# POWER_SUPPLY.net
KiCad netlist of a schematic drawn in Altium Designer
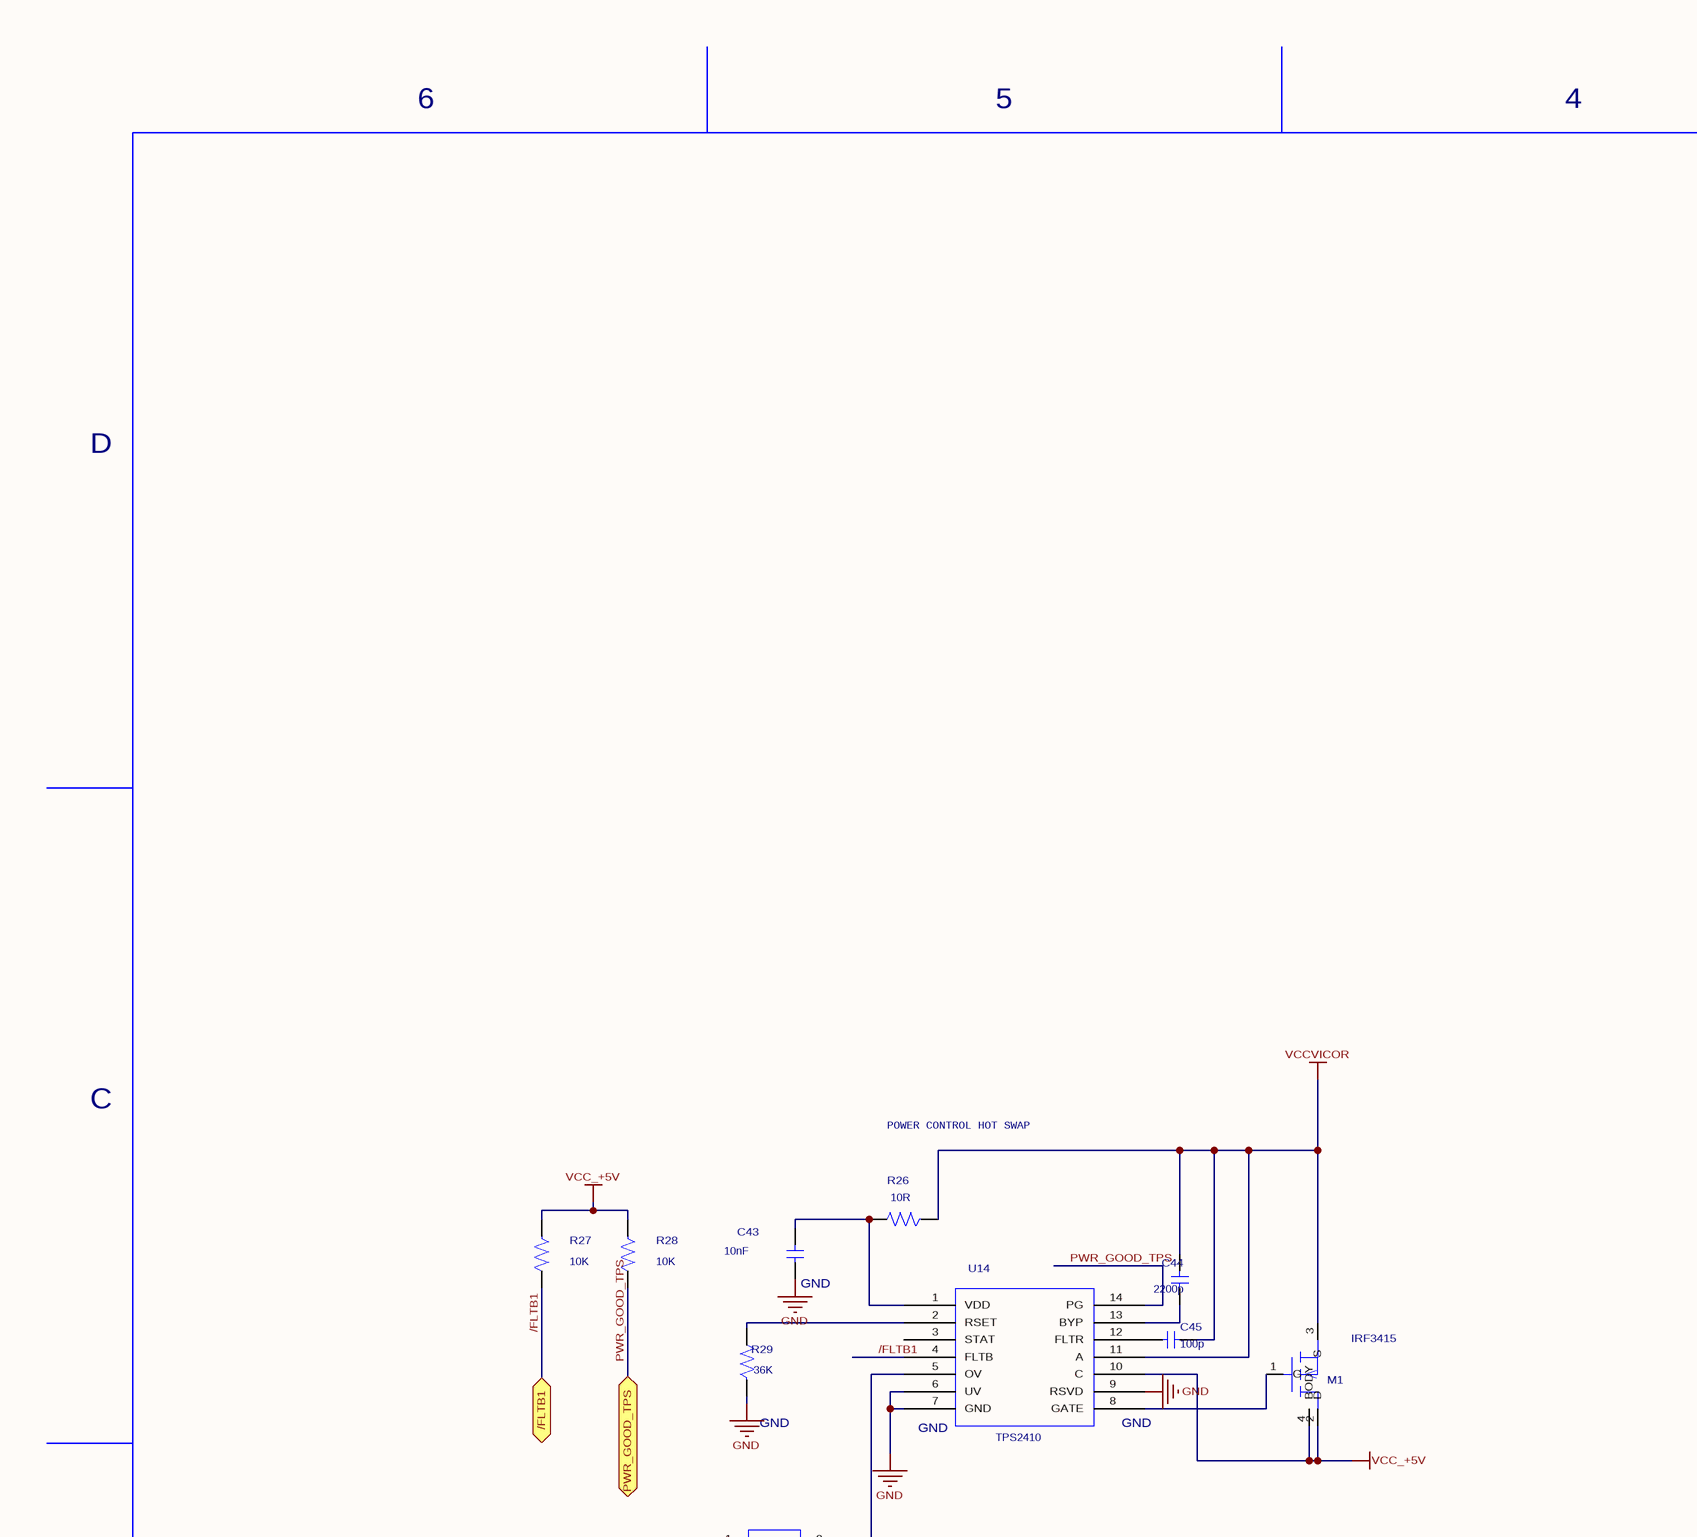
[diagram p0: POWER_SUPPLY.SchDoc, top left]
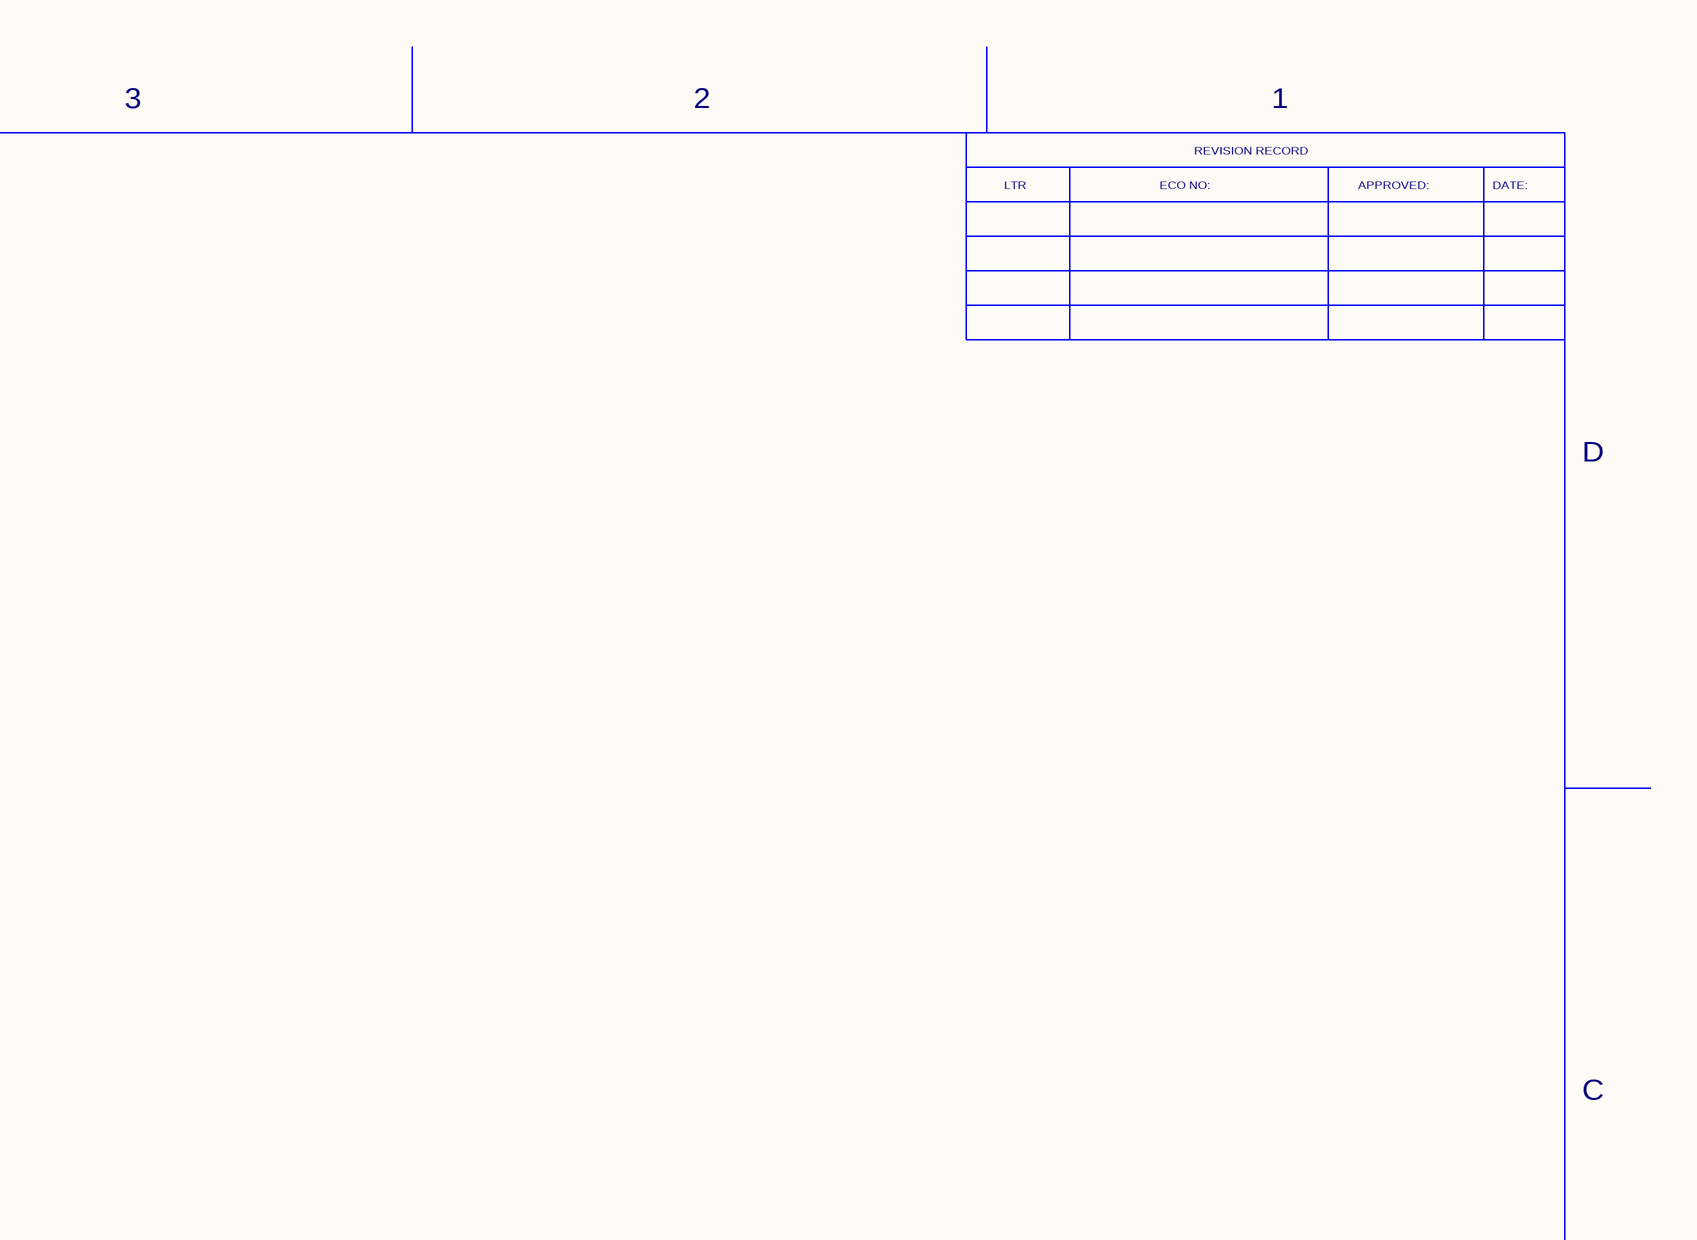
[diagram p1: POWER_SUPPLY.SchDoc, top right]
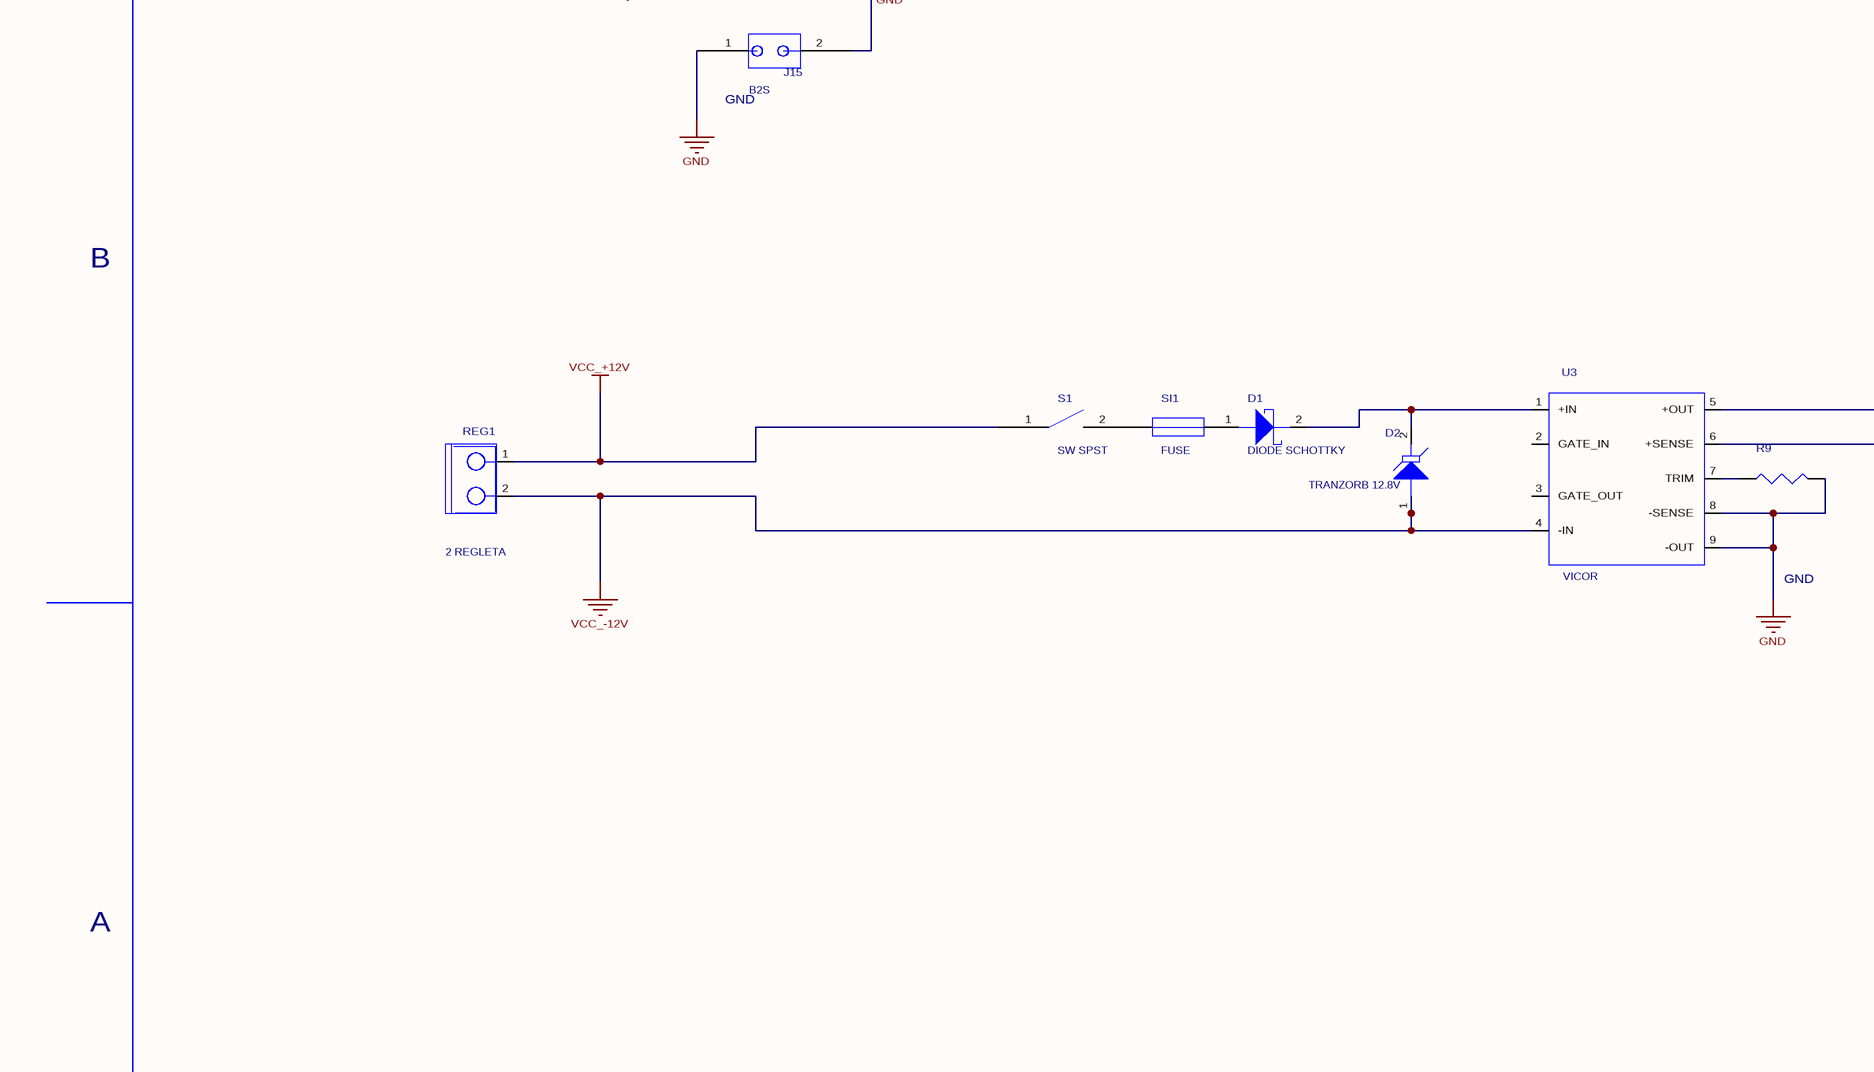
[diagram p2: POWER_SUPPLY.SchDoc, bottom left]
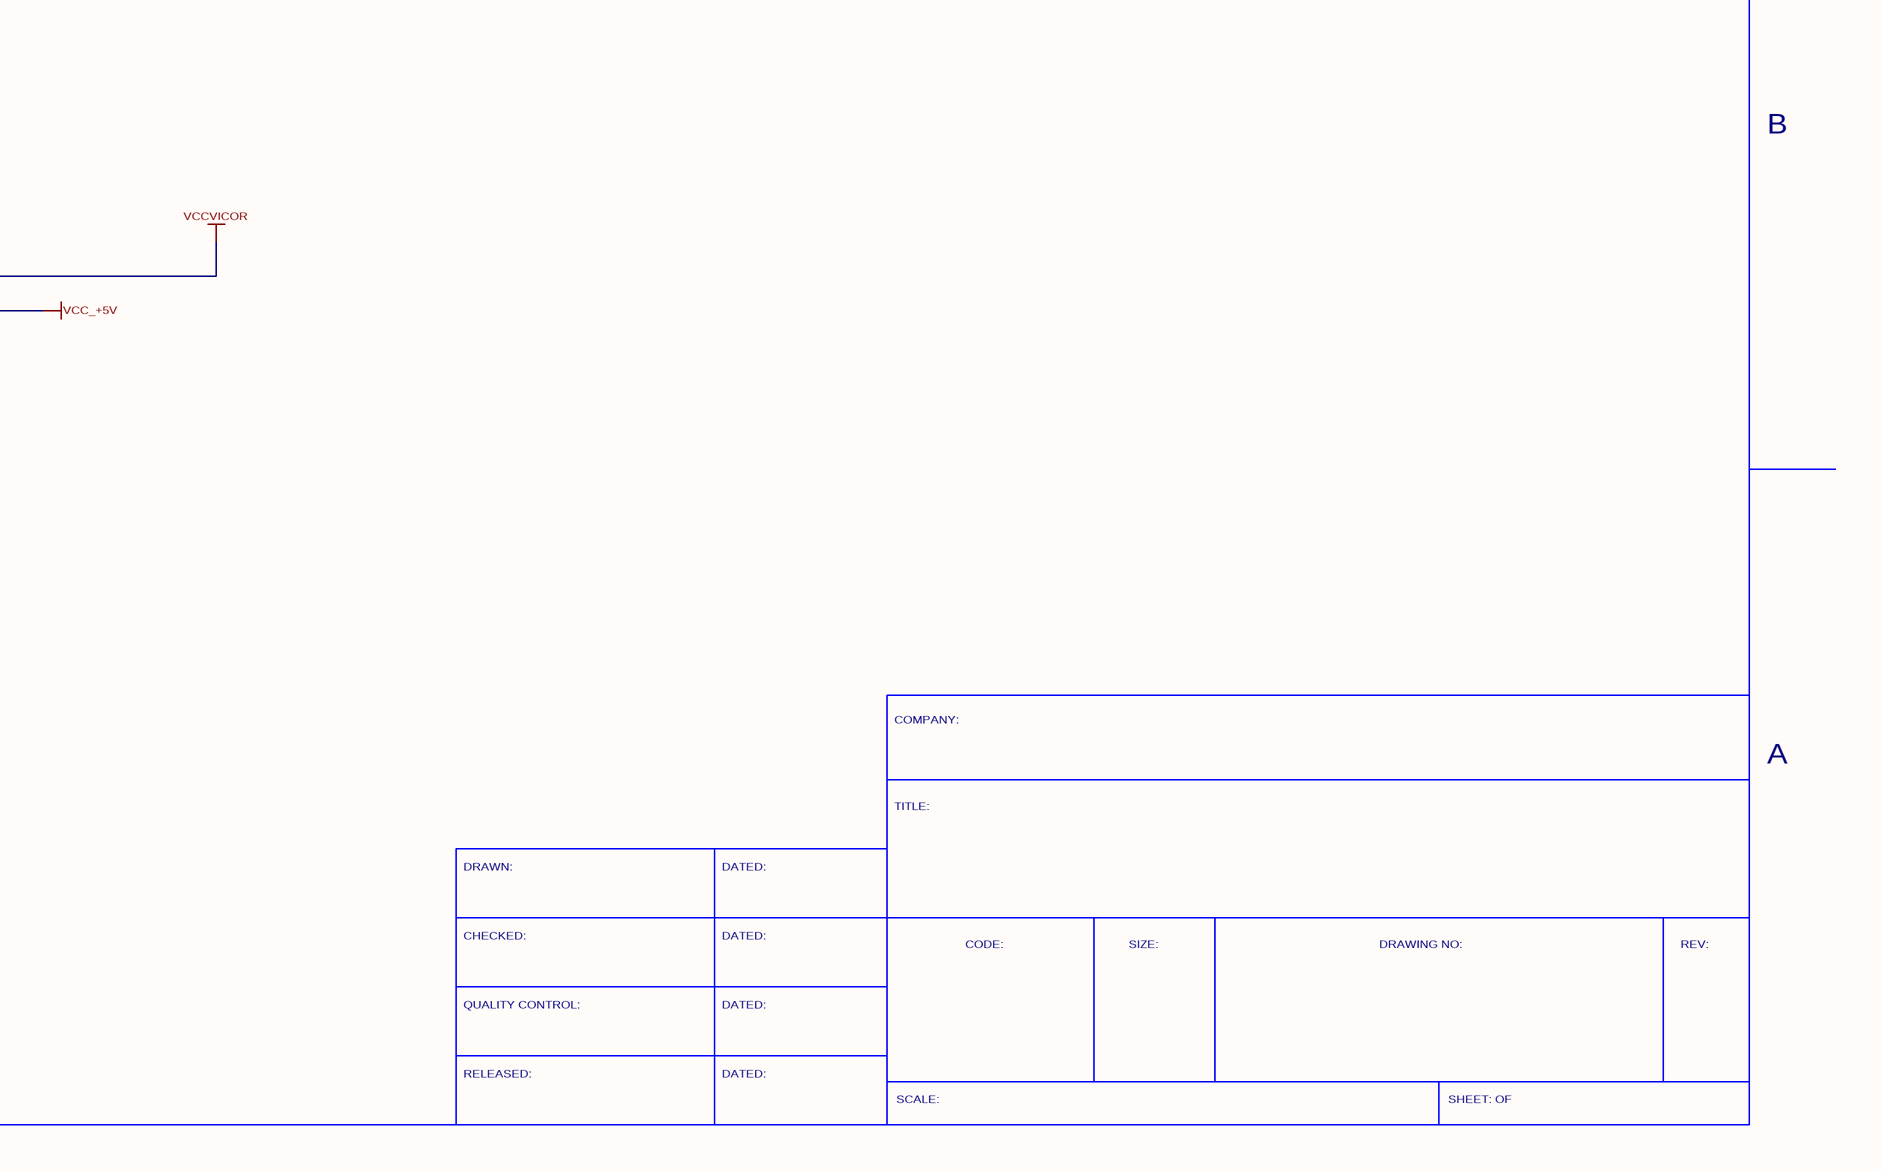
[diagram p3: POWER_SUPPLY.SchDoc, bottom right]

(export (version "E")
  (design (tool "Eeschema 10.0.6"))
  (components
    (comp (ref "C43")
      (value "10nF")
      (footprint "SM/C_0805")
      (fields (field (name "VOLTAGE") "CMAX") (field (name "Comment") "C_3"))
      (libsource (lib "*") (part "C_3"))
    )
    (comp (ref "C44")
      (value "2200p")
      (footprint "SM/C_0805")
      (fields (field (name "VOLTAGE") "CMAX") (field (name "Comment") "C_3"))
      (libsource (lib "*") (part "C_3"))
    )
    (comp (ref "C45")
      (value "100p")
      (footprint "SM/C_0805")
      (fields (field (name "VOLTAGE") "CMAX") (field (name "Comment") "C_3"))
      (libsource (lib "*") (part "C_3"))
    )
    (comp (ref "D1")
      (value "DIODE SCHOTTKY")
      (footprint "SM/DO214AB_21")
      (fields (field (name "Comment") "DIODE_SCHOTTKY_0"))
      (libsource (lib "*") (part "DIODE_SCHOTTKY_0"))
    )
    (comp (ref "D2")
      (value "TRANZORB 12.8V")
      (footprint "SM/DO214AC_21")
      (fields (field (name "Comment") "TRANZORB_0"))
      (libsource (lib "*") (part "TRANZORB_0"))
    )
    (comp (ref "J15")
      (value "B2S")
      (footprint "JUMPER_100")
      (fields (field (name "Comment") "B2S_0"))
      (libsource (lib "*") (part "B2S_0"))
    )
    (comp (ref "M1")
      (value "IRF3415")
      (footprint "IRF3415_PADS_REV1")
      (fields (field (name "Comment") "IRF3415_BODY"))
      (libsource (lib "*") (part "IRF3415_BODY"))
    )
    (comp (ref "R9") (value "RESISTOR") (footprint "SM/R_1206") (libsource (lib "*") (part "RESISTOR")))
    (comp (ref "R26")
      (value "10R")
      (footprint "SM/R_1206")
      (fields (field (name "VOLTAGE") "RVMAX") (field (name "POWER") "RMAX") (field (name "Comment") "R"))
      (libsource (lib "*") (part "R"))
    )
    (comp (ref "R27")
      (value "10K")
      (footprint "SM/R_1206")
      (fields (field (name "VOLTAGE") "RVMAX") (field (name "POWER") "RMAX") (field (name "Comment") "R"))
      (libsource (lib "*") (part "R"))
    )
    (comp (ref "R28")
      (value "10K")
      (footprint "SM/R_1206")
      (fields (field (name "VOLTAGE") "RVMAX") (field (name "POWER") "RMAX") (field (name "Comment") "R"))
      (libsource (lib "*") (part "R"))
    )
    (comp (ref "R29")
      (value "36K")
      (footprint "SM/R_1206")
      (fields (field (name "VOLTAGE") "RVMAX") (field (name "POWER") "RMAX") (field (name "Comment") "R"))
      (libsource (lib "*") (part "R"))
    )
    (comp (ref "REG1")
      (value "2 REGLETA")
      (footprint "REG2_REV8")
      (fields (field (name "Comment") "8_REGLETA_4"))
      (libsource (lib "*") (part "8_REGLETA_4"))
    )
    (comp (ref "S1")
      (value "SW SPST")
      (footprint "SW12V_REV2")
      (fields (field (name "Comment") "SW_SPST_0"))
      (libsource (lib "*") (part "SW_SPST_0"))
    )
    (comp (ref "SI1") (value "FUSE") (footprint "FUSEHOLDER3") (libsource (lib "*") (part "FUSE")))
    (comp (ref "U3") (value "VICOR") (footprint "VIKOR1") (libsource (lib "*") (part "VICOR")))
    (comp (ref "U14")
      (value "TPS2410")
      (footprint "PDSO-G14_REV7")
      (fields (field (name "Comment") "TPS2410_1"))
      (libsource (lib "*") (part "TPS2410_1"))
    )
  )
  (nets
    (net (code "1") (name "/PWR_GOOD_TPS") (class "Default")
      (node (ref "R28") (pin "2") (pinfunction "2_2") (pintype "passive"))
      (node (ref "U14") (pin "14") (pinfunction "PG_14") (pintype "open_collector"))
    )
    (net (code "2") (name "/{slash}FLTB1") (class "Default")
      (node (ref "R27") (pin "2") (pinfunction "2_2") (pintype "passive"))
      (node (ref "U14") (pin "4") (pinfunction "FLTB_4") (pintype "passive"))
    )
    (net (code "3") (name "GND") (class "Default")
      (node (ref "C43") (pin "1") (pinfunction "1_1") (pintype "passive"))
      (node (ref "J15") (pin "1") (pinfunction "1_1") (pintype "passive"))
      (node (ref "R29") (pin "1") (pinfunction "1_1") (pintype "passive"))
      (node (ref "R9") (pin "2") (pinfunction "2_2") (pintype "passive"))
      (node (ref "U14") (pin "6") (pinfunction "UV_6") (pintype "passive"))
      (node (ref "U14") (pin "7") (pinfunction "GND_7") (pintype "passive"))
      (node (ref "U14") (pin "9") (pinfunction "RSVD_9") (pintype "passive"))
      (node (ref "U3") (pin "8") (pinfunction "-SENSE_8") (pintype "passive"))
      (node (ref "U3") (pin "9") (pinfunction "-OUT_9") (pintype "power_in"))
    )
    (net (code "4") (name "Net-(D1-ANODE)") (class "Default")
      (node (ref "D1") (pin "1") (pinfunction "ANODE_1") (pintype "passive"))
      (node (ref "SI1") (pin "2") (pinfunction "2_2") (pintype "passive"))
    )
    (net (code "5") (name "Net-(D1-CATHODE)") (class "Default")
      (node (ref "D1") (pin "2") (pinfunction "CATHODE_2") (pintype "passive"))
      (node (ref "D2") (pin "2") (pinfunction "CATHODE_2") (pintype "passive"))
      (node (ref "U3") (pin "1") (pinfunction "+IN_1") (pintype "power_in"))
    )
    (net (code "6") (name "Net-(M1-G)") (class "Default")
      (node (ref "M1") (pin "1") (pinfunction "G_1") (pintype "passive"))
      (node (ref "U14") (pin "8") (pinfunction "GATE_8") (pintype "passive"))
    )
    (net (code "7") (name "Net-(S1-NO)") (class "Default")
      (node (ref "S1") (pin "2") (pinfunction "NO_2") (pintype "passive"))
      (node (ref "SI1") (pin "1") (pinfunction "1_1") (pintype "passive"))
    )
    (net (code "8") (name "Net-(U3-TRIM)") (class "Default")
      (node (ref "R9") (pin "1") (pinfunction "1_1") (pintype "passive"))
      (node (ref "U3") (pin "7") (pinfunction "TRIM_7") (pintype "passive"))
    )
    (net (code "9") (name "Net-(U14-BYP)") (class "Default")
      (node (ref "C44") (pin "1") (pinfunction "1_1") (pintype "passive"))
      (node (ref "U14") (pin "13") (pinfunction "BYP_13") (pintype "passive"))
    )
    (net (code "10") (name "Net-(U14-FLTR)") (class "Default")
      (node (ref "C45") (pin "2") (pinfunction "2_2") (pintype "passive"))
      (node (ref "U14") (pin "12") (pinfunction "FLTR_12") (pintype "passive"))
    )
    (net (code "11") (name "Net-(U14-OV)") (class "Default")
      (node (ref "J15") (pin "2") (pinfunction "2_2") (pintype "passive"))
      (node (ref "U14") (pin "5") (pinfunction "OV_5") (pintype "passive"))
    )
    (net (code "12") (name "Net-(U14-RSET)") (class "Default")
      (node (ref "R29") (pin "2") (pinfunction "2_2") (pintype "passive"))
      (node (ref "U14") (pin "2") (pinfunction "RSET_2") (pintype "passive"))
    )
    (net (code "13") (name "Net-(U14-VDD)") (class "Default")
      (node (ref "C43") (pin "2") (pinfunction "2_2") (pintype "passive"))
      (node (ref "R26") (pin "2") (pinfunction "2_2") (pintype "passive"))
      (node (ref "U14") (pin "1") (pinfunction "VDD_1") (pintype "passive"))
    )
    (net (code "14") (name "VCCVICOR") (class "Default")
      (node (ref "C44") (pin "2") (pinfunction "2_2") (pintype "passive"))
      (node (ref "C45") (pin "1") (pinfunction "1_1") (pintype "passive"))
      (node (ref "M1") (pin "3") (pinfunction "S_3") (pintype "passive"))
      (node (ref "R26") (pin "1") (pinfunction "1_1") (pintype "passive"))
      (node (ref "U14") (pin "11") (pinfunction "A_11") (pintype "passive"))
      (node (ref "U3") (pin "5") (pinfunction "+OUT_5") (pintype "power_in"))
    )
    (net (code "15") (name "VCC_+5V") (class "Default")
      (node (ref "M1") (pin "2") (pinfunction "D_2") (pintype "passive"))
      (node (ref "M1") (pin "4") (pinfunction "BODY_4") (pintype "passive"))
      (node (ref "R27") (pin "1") (pinfunction "1_1") (pintype "passive"))
      (node (ref "R28") (pin "1") (pinfunction "1_1") (pintype "passive"))
      (node (ref "U14") (pin "10") (pinfunction "C_10") (pintype "passive"))
      (node (ref "U3") (pin "6") (pinfunction "+SENSE_6") (pintype "passive"))
    )
    (net (code "16") (name "VCC_+12V") (class "Default")
      (node (ref "REG1") (pin "1") (pinfunction "1_1") (pintype "passive"))
      (node (ref "S1") (pin "1") (pinfunction "COMMON_1") (pintype "passive"))
    )
    (net (code "17") (name "VCC_-12V") (class "Default")
      (node (ref "D2") (pin "1") (pinfunction "ANODE_1") (pintype "passive"))
      (node (ref "REG1") (pin "2") (pinfunction "2_2") (pintype "passive"))
      (node (ref "U3") (pin "4") (pinfunction "-IN_4") (pintype "power_in"))
    )
    (net (code "18") (name "unconnected-(U3-GATE_IN-Pad2)") (class "Default")
      (node (ref "U3") (pin "2") (pinfunction "GATE_IN_2") (pintype "passive"))
    )
    (net (code "19") (name "unconnected-(U3-GATE_OUT-Pad3)") (class "Default")
      (node (ref "U3") (pin "3") (pinfunction "GATE_OUT_3") (pintype "passive"))
    )
    (net (code "20") (name "unconnected-(U14-STAT-Pad3)") (class "Default")
      (node (ref "U14") (pin "3") (pinfunction "STAT_3") (pintype "passive"))
    )
  )
)
